# SCH_krish_s-candle.net
KiCad netlist of a schematic drawn in EasyEDA
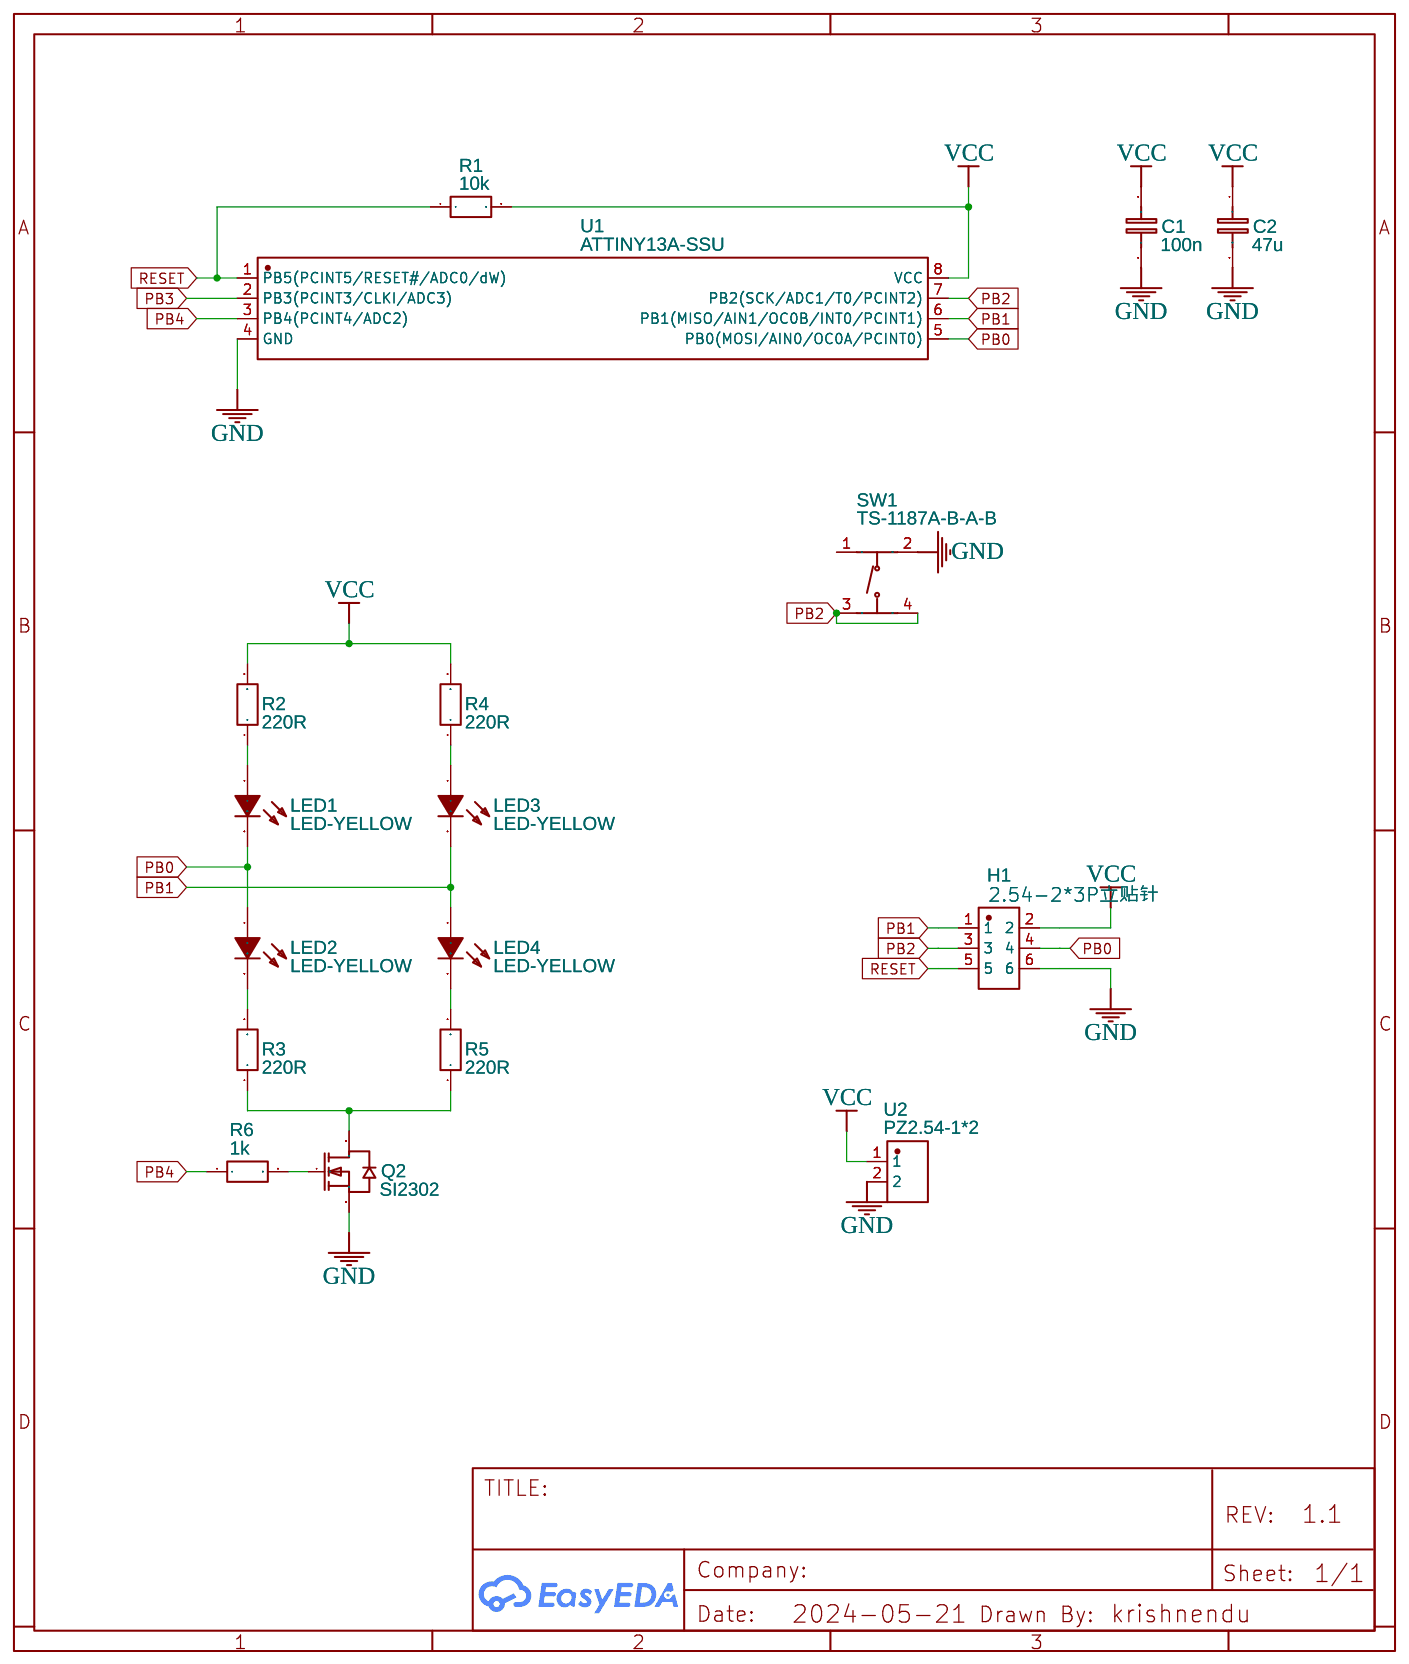
[diagram p0: schematic sheet]

(export (version "E")
  (design (tool "Eeschema 10.0.6"))
  (components
    (comp (ref "C1")
      (value "100n")
      (fields (field (name "Manufacturer Part") "CC0603KRX7R9BB104") (field (name "Manufacturer") "YAGEO"))
      (libsource (lib "") (part "Cap_0603_EU"))
    )
    (comp (ref "C2")
      (value "47u")
      (fields (field (name "Manufacturer Part") "1206F476M160NT") (field (name "Manufacturer") "FH"))
      (libsource (lib "") (part "Cap_1206_EU"))
    )
    (comp (ref "H1")
      (value "2.54-2*3P立贴针")
      (fields (field (name "Manufacturer") "BOOMELE(博穆精密)"))
      (libsource (lib "") (part "2.54-2*3P立贴针"))
    )
    (comp (ref "LED1")
      (value "LED-YELLOW")
      (fields
        (field (name "Manufacturer Part") "204-10UYD/S530-A3-L")
        (field (name "Manufacturer") "EVERLIGHT")
      )
      (libsource (lib "") (part "LED-0603-YELLOW"))
    )
    (comp (ref "LED2")
      (value "LED-YELLOW")
      (fields
        (field (name "Manufacturer Part") "204-10UYD/S530-A3-L")
        (field (name "Manufacturer") "EVERLIGHT")
      )
      (libsource (lib "") (part "LED-0603-YELLOW"))
    )
    (comp (ref "LED3")
      (value "LED-YELLOW")
      (fields
        (field (name "Manufacturer Part") "204-10UYD/S530-A3-L")
        (field (name "Manufacturer") "EVERLIGHT")
      )
      (libsource (lib "") (part "LED-0603-YELLOW"))
    )
    (comp (ref "LED4")
      (value "LED-YELLOW")
      (fields
        (field (name "Manufacturer Part") "204-10UYD/S530-A3-L")
        (field (name "Manufacturer") "EVERLIGHT")
      )
      (libsource (lib "") (part "LED-0603-YELLOW"))
    )
    (comp (ref "Q2")
      (value "SI2302")
      (fields (field (name "Manufacturer") "Bourne Semicon (Shenzhen)"))
      (libsource (lib "") (part "SI2302_C344009"))
    )
    (comp (ref "R1")
      (value "10k")
      (fields (field (name "Manufacturer Part") "0603WAF1002T5E") (field (name "Manufacturer") "UniOhm"))
      (libsource (lib "") (part "Res_0603(1/10W)_EU_1"))
    )
    (comp (ref "R2")
      (value "220R")
      (fields (field (name "Manufacturer Part") "0603WAF2200T5E") (field (name "Manufacturer") "UniOhm"))
      (libsource (lib "") (part "Res_0603(1/10W)_EU"))
    )
    (comp (ref "R3")
      (value "220R")
      (fields (field (name "Manufacturer Part") "0603WAF2200T5E") (field (name "Manufacturer") "UniOhm"))
      (libsource (lib "") (part "Res_0603(1/10W)_EU"))
    )
    (comp (ref "R4")
      (value "220R")
      (fields (field (name "Manufacturer Part") "0603WAF2200T5E") (field (name "Manufacturer") "UniOhm"))
      (libsource (lib "") (part "Res_0603(1/10W)_EU"))
    )
    (comp (ref "R5")
      (value "220R")
      (fields (field (name "Manufacturer Part") "0603WAF2200T5E") (field (name "Manufacturer") "UniOhm"))
      (libsource (lib "") (part "Res_0603(1/10W)_EU"))
    )
    (comp (ref "R6")
      (value "1k")
      (fields (field (name "Manufacturer Part") "0603WAF1001T5E") (field (name "Manufacturer") "UniOhm"))
      (libsource (lib "") (part "Res_0603(1/10W)_EU_1"))
    )
    (comp (ref "SW1")
      (value "TS-1187A-B-A-B")
      (fields (field (name "Manufacturer") "XKB Connectivity(中国星坤)"))
      (libsource (lib "") (part "TS-1187A-B-A-B"))
    )
    (comp (ref "U1")
      (value "ATTINY13A-SSU")
      (fields (field (name "Manufacturer") "MICROCHIP"))
      (libsource (lib "") (part "Unknown_285_-660"))
    )
    (comp (ref "U2")
      (value "PZ2.54-1*2")
      (fields (field (name "Manufacturer") "ZHOURI(洲日)"))
      (libsource (lib "") (part "PZ2.54-1*2"))
    )
  )
  (nets
    (net (code "1") (name "GND") (class "Default")
      (node (ref "C1") (pin "2") (pinfunction "2_2") (pintype "unspecified"))
      (node (ref "C2") (pin "2") (pinfunction "2_2") (pintype "unspecified"))
      (node (ref "H1") (pin "6") (pinfunction "6_6") (pintype "unspecified"))
      (node (ref "Q2") (pin "2") (pinfunction "S_2") (pintype "unspecified"))
      (node (ref "SW1") (pin "2") (pinfunction "B_2") (pintype "unspecified"))
      (node (ref "U1") (pin "4") (pinfunction "GND_4") (pintype "unspecified"))
      (node (ref "U2") (pin "2") (pinfunction "2_2") (pintype "unspecified"))
    )
    (net (code "2") (name "Net-(LED1-A)") (class "Default")
      (node (ref "LED1") (pin "1") (pinfunction "A_1") (pintype "input"))
      (node (ref "R2") (pin "1") (pinfunction "1_1") (pintype "unspecified"))
    )
    (net (code "3") (name "Net-(LED2-C)") (class "Default")
      (node (ref "LED2") (pin "2") (pinfunction "C_2") (pintype "input"))
      (node (ref "R3") (pin "2") (pinfunction "2_2") (pintype "unspecified"))
    )
    (net (code "4") (name "Net-(LED3-A)") (class "Default")
      (node (ref "LED3") (pin "1") (pinfunction "A_1") (pintype "input"))
      (node (ref "R4") (pin "1") (pinfunction "1_1") (pintype "unspecified"))
    )
    (net (code "5") (name "Net-(LED4-C)") (class "Default")
      (node (ref "LED4") (pin "2") (pinfunction "C_2") (pintype "input"))
      (node (ref "R5") (pin "2") (pinfunction "2_2") (pintype "unspecified"))
    )
    (net (code "6") (name "Net-(Q2-D)") (class "Default")
      (node (ref "Q2") (pin "3") (pinfunction "D_3") (pintype "unspecified"))
      (node (ref "R3") (pin "1") (pinfunction "1_1") (pintype "unspecified"))
      (node (ref "R5") (pin "1") (pinfunction "1_1") (pintype "unspecified"))
    )
    (net (code "7") (name "Net-(Q2-G)") (class "Default")
      (node (ref "Q2") (pin "1") (pinfunction "G_1") (pintype "unspecified"))
      (node (ref "R6") (pin "2") (pinfunction "2_2") (pintype "unspecified"))
    )
    (net (code "8") (name "PB0") (class "Default")
      (node (ref "H1") (pin "4") (pinfunction "4_4") (pintype "unspecified"))
      (node (ref "LED1") (pin "2") (pinfunction "C_2") (pintype "input"))
      (node (ref "LED2") (pin "1") (pinfunction "A_1") (pintype "input"))
      (node (ref "U1") (pin "5") (pinfunction "PB0(MOSI/AIN0/OC0A/PCINT0)_5") (pintype "unspecified"))
    )
    (net (code "9") (name "PB1") (class "Default")
      (node (ref "H1") (pin "1") (pinfunction "1_1") (pintype "unspecified"))
      (node (ref "LED3") (pin "2") (pinfunction "C_2") (pintype "input"))
      (node (ref "LED4") (pin "1") (pinfunction "A_1") (pintype "input"))
      (node (ref "U1") (pin "6") (pinfunction "PB1(MISO/AIN1/OC0B/INT0/PCINT1)_6") (pintype "unspecified"))
    )
    (net (code "10") (name "PB2") (class "Default")
      (node (ref "H1") (pin "3") (pinfunction "3_3") (pintype "unspecified"))
      (node (ref "SW1") (pin "3") (pinfunction "C_3") (pintype "unspecified"))
      (node (ref "SW1") (pin "4") (pinfunction "D_4") (pintype "unspecified"))
      (node (ref "U1") (pin "7") (pinfunction "PB2(SCK/ADC1/T0/PCINT2)_7") (pintype "unspecified"))
    )
    (net (code "11") (name "PB3") (class "Default")
      (node (ref "U1") (pin "2") (pinfunction "PB3(PCINT3/CLKI/ADC3)_2") (pintype "unspecified"))
    )
    (net (code "12") (name "PB4") (class "Default")
      (node (ref "R6") (pin "1") (pinfunction "1_1") (pintype "unspecified"))
      (node (ref "U1") (pin "3") (pinfunction "PB4(PCINT4/ADC2)_3") (pintype "unspecified"))
    )
    (net (code "13") (name "RESET") (class "Default")
      (node (ref "H1") (pin "5") (pinfunction "5_5") (pintype "unspecified"))
      (node (ref "R1") (pin "1") (pinfunction "1_1") (pintype "unspecified"))
      (node (ref "U1") (pin "1") (pinfunction "PB5(PCINT5/RESET#/ADC0/dW)_1") (pintype "unspecified"))
    )
    (net (code "14") (name "VCC") (class "Default")
      (node (ref "C1") (pin "1") (pinfunction "1_1") (pintype "unspecified"))
      (node (ref "C2") (pin "1") (pinfunction "1_1") (pintype "unspecified"))
      (node (ref "H1") (pin "2") (pinfunction "2_2") (pintype "unspecified"))
      (node (ref "R1") (pin "2") (pinfunction "2_2") (pintype "unspecified"))
      (node (ref "R2") (pin "2") (pinfunction "2_2") (pintype "unspecified"))
      (node (ref "R4") (pin "2") (pinfunction "2_2") (pintype "unspecified"))
      (node (ref "U1") (pin "8") (pinfunction "VCC_8") (pintype "unspecified"))
      (node (ref "U2") (pin "1") (pinfunction "1_1") (pintype "unspecified"))
    )
    (net (code "15") (name "unconnected-(SW1-A-Pad1)") (class "Default")
      (node (ref "SW1") (pin "1") (pinfunction "A_1") (pintype "unspecified"))
    )
  )
)
